# PS.net
KiCad netlist of a schematic drawn in EAGLE
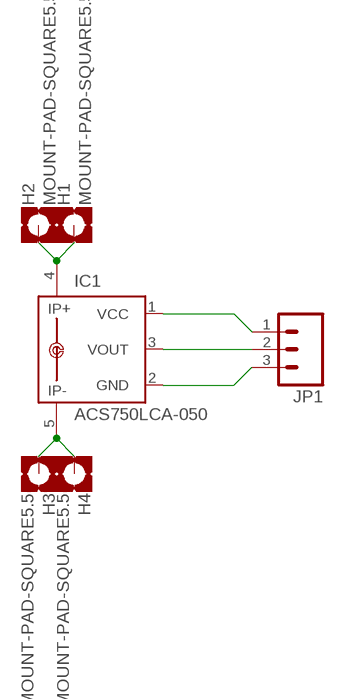
[diagram p0: schematic, sheet 1]

(export (version "E")
  (design (tool "Eeschema 10.0.6"))
  (components
    (comp (ref "H1")
      (value "MOUNT-PAD-SQUARE5.5")
      (footprint "eagle-import:5,5-PAD-SQUARE")
      (libsource (lib "eagle-import") (part "MOUNT-PAD-SQUARE5.5"))
    )
    (comp (ref "H2")
      (value "MOUNT-PAD-SQUARE5.5")
      (footprint "eagle-import:5,5-PAD-SQUARE")
      (libsource (lib "eagle-import") (part "MOUNT-PAD-SQUARE5.5"))
    )
    (comp (ref "H3")
      (value "MOUNT-PAD-SQUARE5.5")
      (footprint "eagle-import:5,5-PAD-SQUARE")
      (libsource (lib "eagle-import") (part "MOUNT-PAD-SQUARE5.5"))
    )
    (comp (ref "H4")
      (value "MOUNT-PAD-SQUARE5.5")
      (footprint "eagle-import:5,5-PAD-SQUARE")
      (libsource (lib "eagle-import") (part "MOUNT-PAD-SQUARE5.5"))
    )
    (comp (ref "IC1")
      (value "ACS750LCA-050")
      (footprint "eagle-import:ACS75050")
      (fields (field (name "MF") "ALLEGRO MICROSYSTEMS, INC."))
      (libsource (lib "eagle-import") (part "ACS750CA-050L"))
    )
    (comp (ref "JP1")
      (value "M03POLAR_LOCK")
      (footprint "eagle-import:MOLEX-1X3_LOCK")
      (libsource (lib "eagle-import") (part "M03POLAR_LOCK"))
    )
  )
  (nets
    (net (code "1") (name "Net-(H1-MOUNT)") (class "Default")
      (node (ref "H1") (pin "B5,5") (pinfunction "MOUNT_B5,5") (pintype "passive"))
      (node (ref "H2") (pin "B5,5") (pinfunction "MOUNT_B5,5") (pintype "passive"))
      (node (ref "IC1") (pin "4") (pinfunction "IP+_4") (pintype "passive"))
    )
    (net (code "2") (name "Net-(H3-MOUNT)") (class "Default")
      (node (ref "H3") (pin "B5,5") (pinfunction "MOUNT_B5,5") (pintype "passive"))
      (node (ref "H4") (pin "B5,5") (pinfunction "MOUNT_B5,5") (pintype "passive"))
      (node (ref "IC1") (pin "5") (pinfunction "IP-_5") (pintype "passive"))
    )
    (net (code "3") (name "Net-(IC1-GND)") (class "Default")
      (node (ref "IC1") (pin "2") (pinfunction "GND_2") (pintype "power_in"))
      (node (ref "JP1") (pin "3") (pinfunction "3_3") (pintype "passive"))
    )
    (net (code "4") (name "Net-(IC1-VCC)") (class "Default")
      (node (ref "IC1") (pin "1") (pinfunction "VCC_1") (pintype "power_in"))
      (node (ref "JP1") (pin "1") (pinfunction "1_1") (pintype "passive"))
    )
    (net (code "5") (name "Net-(IC1-VOUT)") (class "Default")
      (node (ref "IC1") (pin "3") (pinfunction "VOUT_3") (pintype "output"))
      (node (ref "JP1") (pin "2") (pinfunction "2_2") (pintype "passive"))
    )
    (net (code "6") (name "unconnected-(IC1-PadIP+1)") (class "Default")
      (node (ref "IC1") (pin "IP+1") (pinfunction "IP+1_IP+1") (pintype "input"))
    )
    (net (code "7") (name "unconnected-(IC1-PadIP-1)") (class "Default")
      (node (ref "IC1") (pin "IP-1") (pinfunction "IP-1_IP-1") (pintype "input"))
    )
  )
)
